# WX0_012_296DL_3.net
KiCad netlist of a schematic drawn in Altium Designer
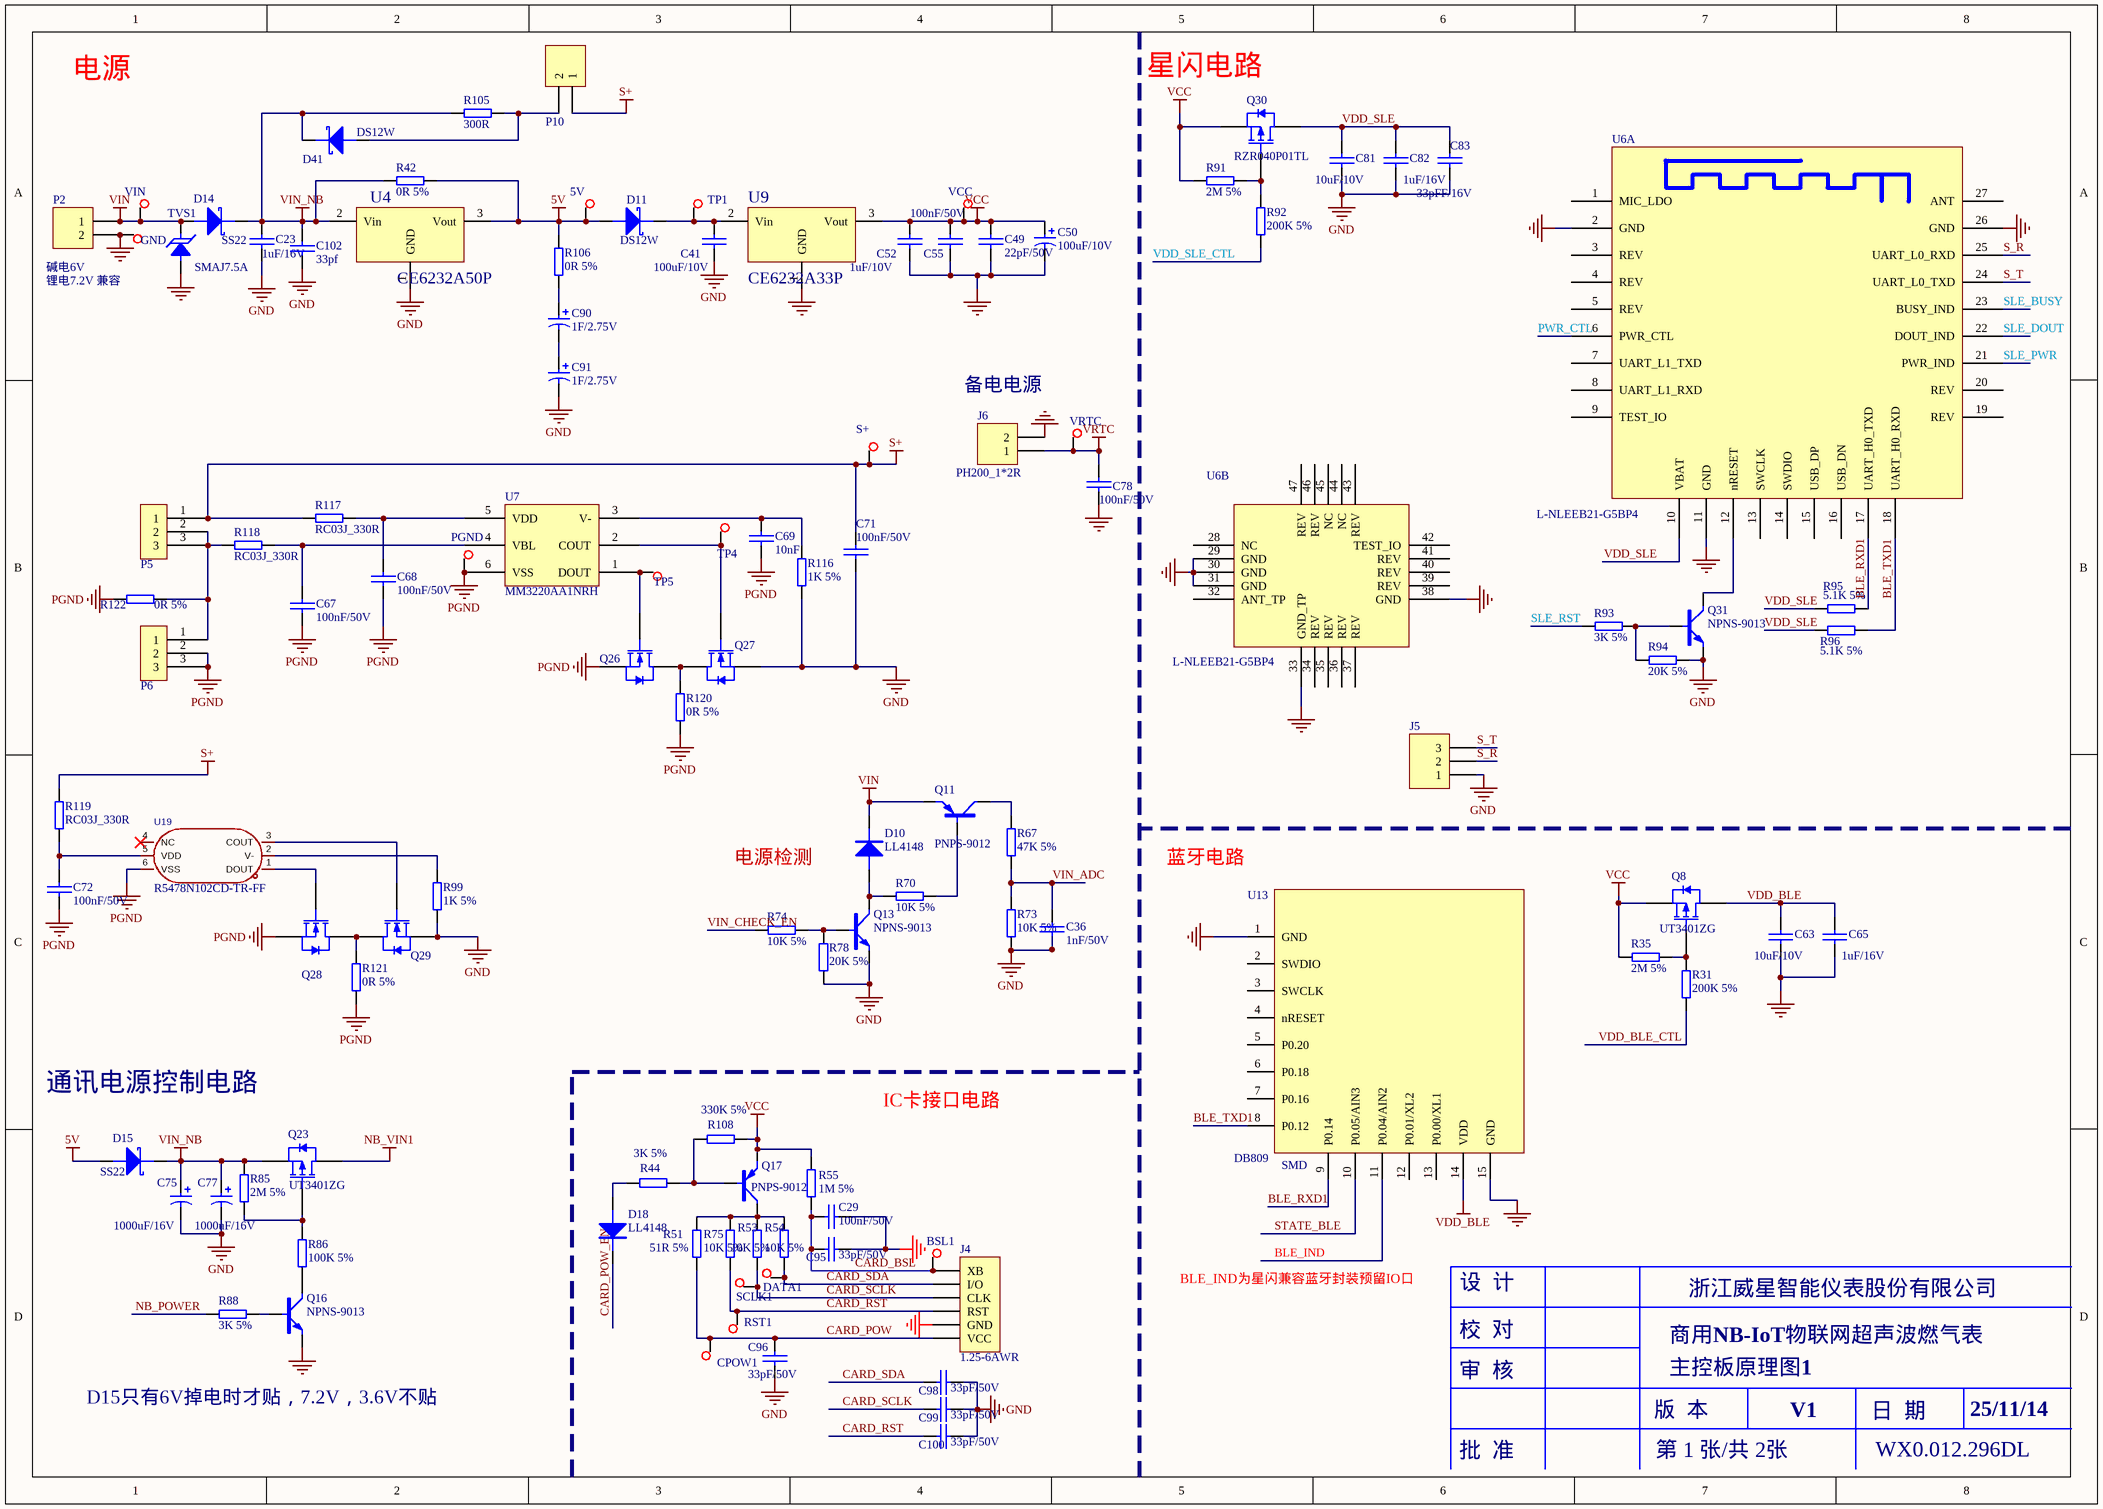
[diagram p0: WX0.012.296DL(3).SchDoc]

(export (version "E")
  (design (tool "Eeschema 10.0.6"))
  (components
    (comp (ref "5V")
      (value "TEST-PAD")
      (footprint "TEST-PAD")
      (description "单面焊盘测试点")
      (fields (field (name "PART NUMBER") "AD_WXHJ_TEST-PAD_01"))
      (libsource (lib "Database_Libs2") (part "TEST-PAD"))
    )
    (comp (ref "BSL1")
      (value "TEST-PAD")
      (footprint "TEST-PAD")
      (description "单面焊盘测试点")
      (fields (field (name "PART NUMBER") "AD_WXHJ_TEST-PAD_01"))
      (libsource (lib "Database_Libs2") (part "TEST-PAD"))
    )
    (comp (ref "C23")
      (value "1uF/16V")
      (footprint "CAP0603")
      (description "105pF,16 V,±10%,0603,国巨,CC0603KRX7R7BB105")
      (fields (field (name "PART NUMBER") "101020103-0003"))
      (libsource (lib "Database_Libs2") (part "CC03K7R7_1U"))
    )
    (comp (ref "C29")
      (value "100nF/50V")
      (footprint "CAP0603")
      (description "104pF,50 V,±10%,0603,国巨,CC0603KRX7R9BB104")
      (fields (field (name "PART NUMBER") "101020103-0021"))
      (libsource (lib "Database_Libs2") (part "CC03K7R9_100N"))
    )
    (comp (ref "C36")
      (value "1nF/50V")
      (footprint "CAP0603")
      (description "102pF,50 V,±10%,0603,国巨,CC0603KRX7R9BB102")
      (fields (field (name "PART NUMBER") "101020103-0022"))
      (libsource (lib "Database_Libs2") (part "CC03K7R9_1N"))
    )
    (comp (ref "C41")
      (value "100uF/10V")
      (footprint "GRM31CR60J107ME39L")
      (description "106pF,10 V,±10%,0603,村田,GRM188R61A106KE47D")
      (fields (field (name "PART NUMBER") "101020103-0026"))
      (libsource (lib "Database_Libs2") (part "CC03K5R6_10U"))
    )
    (comp (ref "C49")
      (value "22pF/50V")
      (footprint "CAP0603")
      (description "22pF,50 V,±5%,0603,国巨,CC0603JRNPO9BN22")
      (fields (field (name "PART NUMBER") "101020103-0009"))
      (libsource (lib "Database_Libs2") (part "CC03JPO9_22P"))
    )
    (comp (ref "C50")
      (value "100uF/10V")
      (footprint "GRM31CR60J107ME39L")
      (description "100UF,10 V,±20%,3528,AVX / KEMET,TAJB107M010RNJ")
      (fields (field (name "PART NUMBER") "1010205-0006"))
      (libsource (lib "Database_Libs2") (part "CT6MATAJ_100U"))
    )
    (comp (ref "C52")
      (value "1uF/10V")
      (footprint "CAP0603")
      (description "106pF,10 V,±10%,0603,村田,GRM188R61A106KE47D")
      (fields (field (name "PART NUMBER") "101020103-0026"))
      (libsource (lib "Database_Libs2") (part "CC03K5R6_10U"))
    )
    (comp (ref "C55")
      (value "100nF/50V")
      (footprint "CAP0603")
      (description "104pF,50 V,±10%,0603,国巨,CC0603KRX7R9BB104")
      (fields (field (name "PART NUMBER") "101020103-0021"))
      (libsource (lib "Database_Libs2") (part "CC03K7R9_100N"))
    )
    (comp (ref "C63")
      (value "10uF/10V")
      (footprint "CAP0603")
      (description "106pF,10 V,±10%,0603,村田,GRM188R61A106KE47D")
      (fields (field (name "PART NUMBER") "101020103-0026"))
      (libsource (lib "Database_Libs2") (part "CC03K5R6_10U"))
    )
    (comp (ref "C65")
      (value "1uF/16V")
      (footprint "CAP0603")
      (description "105pF,16 V,±10%,0603,国巨,CC0603KRX7R7BB105")
      (fields (field (name "PART NUMBER") "101020103-0003"))
      (libsource (lib "Database_Libs2") (part "CC03K7R7_1U"))
    )
    (comp (ref "C67")
      (value "100nF/50V")
      (footprint "CAP0603")
      (description "104pF,50 V,±10%,0603,国巨,CC0603KRX7R9BB104")
      (fields (field (name "PART NUMBER") "101020103-0021"))
      (libsource (lib "Database_Libs1") (part "CC03K7R9_100N"))
    )
    (comp (ref "C68")
      (value "100nF/50V")
      (footprint "CAP0603")
      (description "104pF,50 V,±10%,0603,国巨,CC0603KRX7R9BB104")
      (fields (field (name "PART NUMBER") "101020103-0021"))
      (libsource (lib "Database_Libs1") (part "CC03K7R9_100N"))
    )
    (comp (ref "C69")
      (value "10nF")
      (footprint "CAP0603")
      (description "103pF,50 V,±10%,0603,国巨,CC0603KRX7R9BB104")
      (libsource (lib "Database_Libs1") (part "CC03K7R9_100N"))
    )
    (comp (ref "C71")
      (value "100nF/50V")
      (footprint "CAP0603")
      (description "104pF,50 V,±10%,0603,国巨,CC0603KRX7R9BB104")
      (fields (field (name "PART NUMBER") "101020103-0021"))
      (libsource (lib "Database_Libs1") (part "CC03K7R9_100N"))
    )
    (comp (ref "C72")
      (value "100nF/50V")
      (footprint "CAP0603")
      (description "104pF,50 V,±10%,0603,国巨,CC0603KRX7R9BB104")
      (fields (field (name "PART NUMBER") "101020103-0021"))
      (libsource (lib "Database_Libs1") (part "CC03K7R9_100N"))
    )
    (comp (ref "C75")
      (value "1000uF/16V")
      (footprint "CAP-SMD_BD10.0-L10.3-W10.3-FD")
      (description "1000uF,16 V,±20%,8*20mm,Rubycon,16ZLH1000M")
      (fields (field (name "PART NUMBER") "1010203-0029"))
      (libsource (lib "Database_Libs2") (part "CAL7MRZLH_1000U_R"))
    )
    (comp (ref "C77")
      (value "1000uF/16V")
      (footprint "CAP-SMD_BD10.0-L10.3-W10.3-FD")
      (description "1000uF,16 V,±20%,8*20mm,Rubycon,16ZLH1000M")
      (fields (field (name "PART NUMBER") "1010203-0029"))
      (libsource (lib "Database_Libs2") (part "CAL7MRZLH_1000U_R"))
    )
    (comp (ref "C78")
      (value "100nF/50V")
      (footprint "CAP0603")
      (description "104pF,50 V,±10%,0603,国巨,CC0603KRX7R9BB104")
      (fields (field (name "PART NUMBER") "101020103-0021"))
      (libsource (lib "Database_Libs2") (part "CC03K7R9_100N"))
    )
    (comp (ref "C81")
      (value "10uF/10V")
      (footprint "CAP0603")
      (description "106pF,10 V,±10%,0603,村田,GRM188R61A106KE47D")
      (fields (field (name "PART NUMBER") "101020103-0026"))
      (libsource (lib "Database_Libs2") (part "CC03K5R6_10U"))
    )
    (comp (ref "C82")
      (value "1uF/16V")
      (footprint "CAP0603")
      (description "105pF,16 V,±10%,0603,国巨,CC0603KRX7R7BB105")
      (fields (field (name "PART NUMBER") "101020103-0003"))
      (libsource (lib "Database_Libs2") (part "CC03K7R7_1U"))
    )
    (comp (ref "C83")
      (value "33pFF/16V")
      (footprint "CAP0603")
      (description "105pF,16 V,±10%,0603,国巨,CC0603KRX7R7BB105")
      (fields (field (name "PART NUMBER") "101020103-0003"))
      (libsource (lib "Database_Libs2") (part "CC03K7R7_1U"))
    )
    (comp (ref "C90")
      (value "1F/2.75V")
      (footprint "CAPPC_350_800_1600")
      (description "1F,2.75 V,-20%~+20%,8mm*16mm,红宝石,2.7 DMC 1 M MY4 8X16")
      (fields (field (name "PART NUMBER") "1010202-0015"))
      (libsource (lib "Database_Libs2") (part "CALM3MRDMC_1F"))
    )
    (comp (ref "C91")
      (value "1F/2.75V")
      (footprint "CAPPC_350_800_1600")
      (description "1F,2.75 V,-20%~+20%,8mm*16mm,红宝石,2.7 DMC 1 M MY4 8X16")
      (fields (field (name "PART NUMBER") "1010202-0015"))
      (libsource (lib "Database_Libs2") (part "CALM3MRDMC_1F"))
    )
    (comp (ref "C95")
      (value "33pF/50V")
      (footprint "CAP0603")
      (description "33pF,50 V,±10%,0603,国巨,CC0603KRNPO9BN33")
      (fields (field (name "PART NUMBER") "101020103-0027"))
      (libsource (lib "Database_Libs2") (part "CC03KPO9_33P"))
    )
    (comp (ref "C96")
      (value "33pF/50V")
      (footprint "CAP0603")
      (description "33pF,50 V,±10%,0603,国巨,CC0603KRNPO9BN33")
      (fields (field (name "PART NUMBER") "101020103-0027"))
      (libsource (lib "Database_Libs2") (part "CC03KPO9_33P"))
    )
    (comp (ref "C98")
      (value "33pF/50V")
      (footprint "CAP0603")
      (description "33pF,50 V,±10%,0603,国巨,CC0603KRNPO9BN33")
      (fields (field (name "PART NUMBER") "101020103-0027"))
      (libsource (lib "Database_Libs2") (part "CC03KPO9_33P"))
    )
    (comp (ref "C99")
      (value "33pF/50V")
      (footprint "CAP0603")
      (description "33pF,50 V,±10%,0603,国巨,CC0603KRNPO9BN33")
      (fields (field (name "PART NUMBER") "101020103-0027"))
      (libsource (lib "Database_Libs2") (part "CC03KPO9_33P"))
    )
    (comp (ref "C100")
      (value "33pF/50V")
      (footprint "CAP0603")
      (description "33pF,50 V,±10%,0603,国巨,CC0603KRNPO9BN33")
      (fields (field (name "PART NUMBER") "101020103-0027"))
      (libsource (lib "Database_Libs2") (part "CC03KPO9_33P"))
    )
    (comp (ref "C102")
      (value "33pf")
      (footprint "CAP0603")
      (description "105pF,16 V,±10%,0603,国巨,CC0603KRX7R7BB105")
      (fields (field (name "PART NUMBER") "101020103-0003"))
      (libsource (lib "Database_Libs2") (part "CC03K7R7_1U"))
    )
    (comp (ref "CPOW1")
      (value "TEST-PAD")
      (footprint "TEST-PAD")
      (description "单面焊盘测试点")
      (fields (field (name "PART NUMBER") "AD_WXHJ_TEST-PAD_01"))
      (libsource (lib "Database_Libs2") (part "TEST-PAD"))
    )
    (comp (ref "D10")
      (value "LL4148")
      (footprint "SOD-123FL")
      (description "4148,4148,0.2 A,1 V,100 V,先科,LL4148")
      (fields (field (name "PART NUMBER") "101040101-0005"))
      (libsource (lib "Database_Libs2") (part "02_LL4148"))
    )
    (comp (ref "D11")
      (value "DS12W")
      (footprint "SOD-123FL")
      (description "DS12W,SOD-123FL,1 A,0.55 V,20 V,领晨科技,DS12W")
      (fields (field (name "PART NUMBER") "101040101-0048"))
      (libsource (lib "Database_Libs2") (part "02_DS12W"))
    )
    (comp (ref "D14")
      (value "SS22")
      (footprint "DO-214AC")
      (description "SS12,DO-214AC,1 A,0.55 V,20 V,昶鑫,SS12")
      (fields (field (name "PART NUMBER") "101040101-0009"))
      (libsource (lib "Database_Libs2") (part "02_SS12"))
    )
    (comp (ref "D15")
      (value "SS22")
      (footprint "DO-214AC")
      (description "SS12,DO-214AC,1 A,0.55 V,20 V,昶鑫,SS12")
      (fields (field (name "PART NUMBER") "101040101-0009"))
      (libsource (lib "Database_Libs2") (part "02_SS12"))
    )
    (comp (ref "D18")
      (value "LL4148")
      (footprint "SOD-123FL")
      (description "4148,4148,0.2 A,1 V,100 V,先科,LL4148")
      (fields (field (name "PART NUMBER") "101040101-0005"))
      (libsource (lib "Database_Libs2") (part "02_LL4148"))
    )
    (comp (ref "D41")
      (value "DS12W")
      (footprint "SOD-123FL")
      (description "DS12W,SOD-123FL,1 A,0.55 V,20 V,领晨科技,DS12W")
      (fields (field (name "PART NUMBER") "101040101-0048"))
      (libsource (lib "Database_Libs2") (part "02_DS12W"))
    )
    (comp (ref "DATA1")
      (value "TEST-PAD")
      (footprint "TEST-PAD")
      (description "单面焊盘测试点")
      (fields (field (name "PART NUMBER") "AD_WXHJ_TEST-PAD_01"))
      (libsource (lib "Database_Libs2") (part "TEST-PAD"))
    )
    (comp (ref "GND")
      (value "TEST-PAD")
      (footprint "TEST-PAD")
      (description "单面焊盘测试点")
      (fields (field (name "PART NUMBER") "AD_WXHJ_TEST-PAD_01"))
      (libsource (lib "Database_Libs2") (part "TEST-PAD"))
    )
    (comp (ref "J4")
      (value "1.25-6AWR")
      (footprint "SMT-1.25-6")
      (description "1.25-6AWR 卷,6针1.25mm,母头,单排,贴片卧式")
      (fields (field (name "PART NUMBER") "1010902-0121"))
      (libsource (lib "Database_Libs2") (part "CARD1608"))
    )
    (comp (ref "J5")
      (value "PIN254_1*3")
      (footprint "PIN254_1*3*WXHJ")
      (libsource (lib "Connect_WX") (part "PIN254_1*3"))
    )
    (comp (ref "J6")
      (value "PH200_1*2R")
      (footprint "WX0.008.919PCB-4.2:BAT")
      (description "2.0-2AW,直插弯座，2PIN，脚间距2mm，带防翘起,公头,单排,2.0-2AW;直插弯座，2PIN,脚间距2mm，带防翘起")
      (fields (field (name "PART NUMBER") "1010902-0105"))
      (libsource (lib "Database_Libs2") (part "PH200_1*2R"))
    )
    (comp (ref "P2")
      (value "碱电6V")
      (footprint "Header 2")
      (description "2.0-2AW,直插弯座，2PIN，脚间距2mm，带防翘起,公头,单排,2.0-2AW;直插弯座，2PIN,脚间距2mm，带防翘起")
      (fields (field (name "PART NUMBER") "1010902-0105"))
      (libsource (lib "Database_Libs1") (part "PH200_1*2R"))
    )
    (comp (ref "P5")
      (value "ER14250")
      (footprint "WX0.009.158PCB-4.2:SPC1520_3")
      (description "F0005Q-LF,1200 mA*h,0,3.6 V,带连接片,1/2AA,不能充电,85 ℃,-60 ℃,ER14250,惠州亿纬锂能股份有限公司")
      (fields (field (name "PART NUMBER") "1011101-0203"))
      (libsource (lib "Database_Libs1") (part "04_BAT1_ER14250_3.6V_3"))
    )
    (comp (ref "P6")
      (value "ER14250")
      (footprint "WX0.009.158PCB-4.2:SPC1520_3")
      (description "F0005Q-LF,1200 mA*h,0,3.6 V,带连接片,1/2AA,不能充电,85 ℃,-60 ℃,ER14250,惠州亿纬锂能股份有限公司")
      (fields (field (name "PART NUMBER") "1011101-0203"))
      (libsource (lib "Database_Libs1") (part "04_BAT1_ER14250_3.6V_3"))
    )
    (comp (ref "P10")
      (value "PH2.0-2P")
      (footprint "WX0.007.406PCB-4.2:PCBComponent_1 - duplicate2")
      (description "PH2.0-2P,2mm间距,母头,单排,PH2.0-2P")
      (fields (field (name "PART NUMBER") "1010902-0117"))
      (libsource (lib "Database_Libs2") (part "PH2.0-2P"))
    )
    (comp (ref "PGND")
      (value "TEST-PAD")
      (footprint "TEST-PAD")
      (description "单面焊盘测试点")
      (fields (field (name "PART NUMBER") "AD_WXHJ_TEST-PAD_01"))
      (libsource (lib "Database_Libs2") (part "TEST-PAD"))
    )
    (comp (ref "Q8")
      (value "UT3401ZG")
      (footprint "SOT-23")
      (description "UT3401ZG,P-MOS,SOT-23,UTC,UT3401ZG")
      (fields (field (name "PART NUMBER") "101040201-0013"))
      (libsource (lib "Database_Libs2") (part "03_P-UT3401ZG"))
    )
    (comp (ref "Q11")
      (value "PNPS-9012")
      (footprint "SOT-23")
      (description "9012,PNP,SOT-23,JCET;长电,S9012")
      (fields (field (name "PART NUMBER") "101040201-0001"))
      (libsource (lib "Database_Libs2") (part "03_PNPS-9012"))
    )
    (comp (ref "Q13")
      (value "NPNS-9013")
      (footprint "SOT-23")
      (description "9013,NPN,SOT-23,长电,S9013")
      (fields (field (name "PART NUMBER") "101040201-0002"))
      (libsource (lib "Database_Libs2") (part "03_NPNS-9013"))
    )
    (comp (ref "Q16")
      (value "NPNS-9013")
      (footprint "SOT-23")
      (description "9013,NPN,SOT-23,长电,S9013")
      (fields (field (name "PART NUMBER") "101040201-0002"))
      (libsource (lib "Database_Libs2") (part "03_NPNS-9013"))
    )
    (comp (ref "Q17")
      (value "PNPS-9012")
      (footprint "SOT-23")
      (description "9012,PNP,SOT-23,JCET;长电,S9012")
      (fields (field (name "PART NUMBER") "101040201-0001"))
      (libsource (lib "Database_Libs2") (part "03_PNPS-9012"))
    )
    (comp (ref "Q23")
      (value "UT3401ZG")
      (footprint "SOT-23")
      (description "UT3401ZG,P-MOS,SOT-23,UTC,UT3401ZG")
      (fields (field (name "PART NUMBER") "101040201-0013"))
      (libsource (lib "Database_Libs2") (part "03_P-UT3401ZG"))
    )
    (comp (ref "Q26")
      (value "RTR025N03TL")
      (footprint "SOT-23")
      (fields (field (name "PART NUMBER") "101040201-0012"))
      (libsource (lib "Database_Libs1") (part "03_N-RTR025N03TL"))
    )
    (comp (ref "Q27")
      (value "RTR025N03TL")
      (footprint "SOT-23")
      (fields (field (name "PART NUMBER") "101040201-0012"))
      (libsource (lib "Database_Libs1") (part "03_N-RTR025N03TL"))
    )
    (comp (ref "Q28")
      (value "RTR025N03TL")
      (footprint "SOT-23")
      (fields (field (name "PART NUMBER") "101040201-0012"))
      (libsource (lib "Database_Libs1") (part "03_N-RTR025N03TL"))
    )
    (comp (ref "Q29")
      (value "RTR025N03TL")
      (footprint "SOT-23")
      (fields (field (name "PART NUMBER") "101040201-0012"))
      (libsource (lib "Database_Libs1") (part "03_N-RTR025N03TL"))
    )
    (comp (ref "Q30")
      (value "RZR040P01TL")
      (footprint "SOT-23")
      (description "RZR040P01TL；1.5v导通,P-MOS,SOT-23,罗姆,RZR040P01TL")
      (fields (field (name "PART NUMBER") "101040201-0010"))
      (libsource (lib "Database_Libs2") (part "03_P-RZR040P01TL"))
    )
    (comp (ref "Q31")
      (value "NPNS-9013")
      (footprint "SOT-23")
      (description "9013,NPN,SOT-23,长电,S9013")
      (fields (field (name "PART NUMBER") "101040201-0002"))
      (libsource (lib "Database_Libs2") (part "03_NPNS-9013"))
    )
    (comp (ref "R31")
      (value "200K 5%")
      (footprint "RES0603")
      (description "10K±5%,1/10W,0603")
      (fields (field (name "PART NUMBER") "101010103-0003"))
      (libsource (lib "Database_Libs1") (part "RC03JF_10K"))
    )
    (comp (ref "R35")
      (value "2M 5%")
      (footprint "RES0603")
      (description "10K±5%,1/10W,0603")
      (fields (field (name "PART NUMBER") "101010103-0003"))
      (libsource (lib "Database_Libs1") (part "RC03JF_10K"))
    )
    (comp (ref "R42")
      (value "0R 5%")
      (footprint "RES1206")
      (description "0Ω,±5%,1/4W,1206,国巨,RC1206JR-070RL")
      (fields (field (name "PART NUMBER") "101010101-0013"))
      (libsource (lib "Database_Libs2") (part "RC06J_0R"))
    )
    (comp (ref "R44")
      (value "3K 5%")
      (footprint "RES0603")
      (description "国巨,±5%,0603,,155 ℃,-55 ℃,RC0603JR-073KL,无铅,100 ppm/℃,1/10W,,3K")
      (fields (field (name "PART NUMBER") "101010103-0006"))
      (libsource (lib "Database_Libs2") (part "RC03J_3K"))
    )
    (comp (ref "R51")
      (value "51R 5%")
      (footprint "RES1206")
      (description "51Ω,±5%,1/4W,1206,国巨,RC1206JR-0751RL")
      (fields (field (name "PART NUMBER") "101010101-0029"))
      (libsource (lib "Database_Libs2") (part "RC06F_51R"))
    )
    (comp (ref "R53")
      (value "10K 5%")
      (footprint "RES0603")
      (description "国巨,±5%,0603,,155 ℃,-55 ℃,RC0603JR-0710KL,无铅,200 ppm/℃,1/10W,,10K")
      (fields (field (name "PART NUMBER") "101010103-0003"))
      (libsource (lib "Database_Libs2") (part "RC03J_10K"))
    )
    (comp (ref "R54")
      (value "10K 5%")
      (footprint "RES0603")
      (description "国巨,±5%,0603,,155 ℃,-55 ℃,RC0603JR-0710KL,无铅,200 ppm/℃,1/10W,,10K")
      (fields (field (name "PART NUMBER") "101010103-0003"))
      (libsource (lib "Database_Libs2") (part "RC03J_10K"))
    )
    (comp (ref "R55")
      (value "1M 5%")
      (footprint "RES0603")
      (description "国巨,±5%,0603,,155 ℃,-55 ℃,RC0603JR-071ML,无铅,200 ppm/℃,1/10W,,1M")
      (fields (field (name "PART NUMBER") "101010103-0002"))
      (libsource (lib "Database_Libs2") (part "RC03J_1M"))
    )
    (comp (ref "R67")
      (value "47K 5%")
      (footprint "RES0603")
      (description "47K,±5%,1/10W,0603,国巨,RC0603JR-0747KL")
      (fields (field (name "PART NUMBER") "101010103-0012"))
      (libsource (lib "Database_Libs2") (part "RC03J_47K"))
    )
    (comp (ref "R70")
      (value "10K 5%")
      (footprint "RES0603")
      (description "国巨,±5%,0603,,155 ℃,-55 ℃,RC0603JR-0710KL,无铅,200 ppm/℃,1/10W,,10K")
      (fields (field (name "PART NUMBER") "101010103-0003"))
      (libsource (lib "Database_Libs2") (part "RC03J_10K"))
    )
    (comp (ref "R73")
      (value "10K 5%")
      (footprint "RES0603")
      (description "国巨,±5%,0603,,155 ℃,-55 ℃,RC0603JR-0710KL,无铅,200 ppm/℃,1/10W,,10K")
      (fields (field (name "PART NUMBER") "101010103-0003"))
      (libsource (lib "Database_Libs2") (part "RC03J_10K"))
    )
    (comp (ref "R74")
      (value "10K 5%")
      (footprint "RES0603")
      (description "国巨,±5%,0603,,155 ℃,-55 ℃,RC0603JR-0710KL,无铅,200 ppm/℃,1/10W,,10K")
      (fields (field (name "PART NUMBER") "101010103-0003"))
      (libsource (lib "Database_Libs2") (part "RC03J_10K"))
    )
    (comp (ref "R75")
      (value "10K 5%")
      (footprint "RES0603")
      (description "国巨,±5%,0603,,155 ℃,-55 ℃,RC0603JR-0710KL,无铅,200 ppm/℃,1/10W,,10K")
      (fields (field (name "PART NUMBER") "101010103-0003"))
      (libsource (lib "Database_Libs2") (part "RC03J_10K"))
    )
    (comp (ref "R78")
      (value "20K 5%")
      (footprint "RES0603")
      (description "国巨,±5%,0603,,155 ℃,-55 ℃,RC0603JR-0720KL,无铅,200 ppm/℃,1/10W,,20K")
      (fields (field (name "PART NUMBER") "101010103-0004"))
      (libsource (lib "Database_Libs2") (part "RC03J_20K"))
    )
    (comp (ref "R85")
      (value "2M 5%")
      (footprint "RES0603")
      (description "国巨,±5%,0603,,155 ℃,-55 ℃,RC0603JR-072ML,含铅,100 ppm/℃,1/10W,,2M")
      (fields (field (name "PART NUMBER") "101010103-0025"))
      (libsource (lib "Database_Libs2") (part "RC03J_2M"))
    )
    (comp (ref "R86")
      (value "100K 5%")
      (footprint "RES0603")
      (description "国巨,±5%,0603,,155 ℃,-55 ℃,RC0603JR-07100KL,无铅,100 ppm/℃,1/10W,,100K")
      (fields (field (name "PART NUMBER") "101010103-0005"))
      (libsource (lib "Database_Libs2") (part "RC03J_100K"))
    )
    (comp (ref "R88")
      (value "3K 5%")
      (footprint "RES0603")
      (description "国巨,±5%,0603,,155 ℃,-55 ℃,RC0603JR-073KL,无铅,100 ppm/℃,1/10W,,3K")
      (fields (field (name "PART NUMBER") "101010103-0006"))
      (libsource (lib "Database_Libs2") (part "RC03J_3K"))
    )
    (comp (ref "R91")
      (value "2M 5%")
      (footprint "RES0603")
      (description "国巨,±5%,0603,,155 ℃,-55 ℃,RC0603JR-072ML,含铅,100 ppm/℃,1/10W,,2M")
      (fields (field (name "PART NUMBER") "101010103-0025"))
      (libsource (lib "Database_Libs2") (part "RC03J_2M"))
    )
    (comp (ref "R92")
      (value "200K 5%")
      (footprint "RES0603")
      (description "200K,±5%,1/10W,0603,国巨,RC0603JR-07200KL")
      (fields (field (name "PART NUMBER") "101010103-0034"))
      (libsource (lib "Database_Libs2") (part "RC03J_200K"))
    )
    (comp (ref "R93")
      (value "3K 5%")
      (footprint "RES0603")
      (description "国巨,±5%,0603,,155 ℃,-55 ℃,RC0603JR-073KL,无铅,100 ppm/℃,1/10W,,3K")
      (fields (field (name "PART NUMBER") "101010103-0006"))
      (libsource (lib "Database_Libs2") (part "RC03J_3K"))
    )
    (comp (ref "R94")
      (value "20K 5%")
      (footprint "RES0603")
      (description "国巨,±5%,0603,,155 ℃,-55 ℃,RC0603JR-0720KL,无铅,200 ppm/℃,1/10W,,20K")
      (fields (field (name "PART NUMBER") "101010103-0004"))
      (libsource (lib "Database_Libs2") (part "RC03J_20K"))
    )
    (comp (ref "R95")
      (value "5.1K 5%")
      (footprint "RES0603")
      (description "国巨,±5%,0603,,155 ℃,55 ℃,RC0603JR-075.1KL,无铅,200 ppm/℃,1/10W,,5.1k")
      (fields (field (name "PART NUMBER") "101010103-0015"))
      (libsource (lib "Database_Libs2") (part "RC03J_5.1K"))
    )
    (comp (ref "R96")
      (value "5.1K 5%")
      (footprint "RES0603")
      (description "国巨,±5%,0603,,155 ℃,55 ℃,RC0603JR-075.1KL,无铅,200 ppm/℃,1/10W,,5.1k")
      (fields (field (name "PART NUMBER") "101010103-0015"))
      (libsource (lib "Database_Libs2") (part "RC03J_5.1K"))
    )
    (comp (ref "R99")
      (value "1K 5%")
      (footprint "RES0603")
      (description "1K,±5%,1/10W,0603,国巨,RC0603JR-071KL")
      (fields (field (name "PART NUMBER") "101010103-0008"))
      (libsource (lib "Database_Libs1") (part "RC03J_1K"))
    )
    (comp (ref "R105")
      (value "300R")
      (footprint "RES1206")
      (description "100R,±5%,1/10W,0603,国巨,RC0603JR-07100RL")
      (fields (field (name "PART NUMBER") "101010103-0022"))
      (libsource (lib "Database_Libs2") (part "RC03J_100R"))
    )
    (comp (ref "R106")
      (value "0R 5%")
      (footprint "RES0603")
      (description "国巨,±5%,0603,,155 ℃,-55 ℃,RC0603J2-070RL,无铅,200 ppm/℃,1/10W,,0R")
      (fields (field (name "PART NUMBER") "101010103-0001"))
      (libsource (lib "Database_Libs2") (part "RC03J_0R"))
    )
    (comp (ref "R108")
      (value "330K 5%")
      (footprint "RES0603")
      (description "国巨,±5%,0603,,155 ℃,-55 ℃,RC0603JR-073KL,无铅,100 ppm/℃,1/10W,,3K")
      (fields (field (name "PART NUMBER") "101010103-0006"))
      (libsource (lib "Database_Libs2") (part "RC03J_3K"))
    )
    (comp (ref "R116")
      (value "1K 5%")
      (footprint "RES0603")
      (description "1K,±5%,1/10W,0603,国巨,RC0603JR-071KL")
      (fields (field (name "PART NUMBER") "101010103-0008"))
      (libsource (lib "Database_Libs1") (part "RC03J_1K"))
    )
    (comp (ref "R117")
      (value "RC03J_330R")
      (footprint "RES1206")
      (libsource (lib "Resistor_WX") (part "RC03J_330R"))
    )
    (comp (ref "R118")
      (value "RC03J_330R")
      (footprint "RES1206")
      (libsource (lib "Resistor_WX") (part "RC03J_330R"))
    )
    (comp (ref "R119")
      (value "RC03J_330R")
      (footprint "RES1206")
      (libsource (lib "Resistor_WX") (part "RC03J_330R"))
    )
    (comp (ref "R120")
      (value "0R 5%")
      (footprint "RES0603")
      (description "国巨,±5%,0603,,155 ℃,-55 ℃,RC0603J2-070RL,无铅,200 ppm/℃,1/10W,,0R")
      (fields (field (name "PART NUMBER") "101010103-0001"))
      (libsource (lib "Database_Libs2") (part "RC03J_0R"))
    )
    (comp (ref "R121")
      (value "0R 5%")
      (footprint "RES0603")
      (description "国巨,±5%,0603,,155 ℃,-55 ℃,RC0603J2-070RL,无铅,200 ppm/℃,1/10W,,0R")
      (fields (field (name "PART NUMBER") "101010103-0001"))
      (libsource (lib "Database_Libs2") (part "RC03J_0R"))
    )
    (comp (ref "R122")
      (value "0R 5%")
      (footprint "RES0603")
      (description "国巨,±5%,0603,,155 ℃,-55 ℃,RC0603J2-070RL,无铅,200 ppm/℃,1/10W,,0R")
      (fields (field (name "PART NUMBER") "101010103-0001"))
      (libsource (lib "Database_Libs2") (part "RC03J_0R"))
    )
    (comp (ref "RST1")
      (value "TEST-PAD")
      (footprint "TEST-PAD")
      (description "单面焊盘测试点")
      (fields (field (name "PART NUMBER") "AD_WXHJ_TEST-PAD_01"))
      (libsource (lib "Database_Libs2") (part "TEST-PAD"))
    )
    (comp (ref "S+")
      (value "TEST-PAD")
      (footprint "TEST-PAD")
      (description "单面焊盘测试点")
      (fields (field (name "PART NUMBER") "AD_WXHJ_TEST-PAD_01"))
      (libsource (lib "Database_Libs2") (part "TEST-PAD"))
    )
    (comp (ref "SCLK1")
      (value "TEST-PAD")
      (footprint "TEST-PAD")
      (description "单面焊盘测试点")
      (fields (field (name "PART NUMBER") "AD_WXHJ_TEST-PAD_01"))
      (libsource (lib "Database_Libs2") (part "TEST-PAD"))
    )
    (comp (ref "TP1")
      (value "TEST-PAD")
      (footprint "TEST-PAD")
      (description "单面焊盘测试点")
      (fields (field (name "PART NUMBER") "AD_WXHJ_TEST-PAD_01"))
      (libsource (lib "Database_Libs2") (part "TEST-PAD"))
    )
    (comp (ref "TP4")
      (value "TEST-PAD")
      (footprint "TEST-PAD")
      (description "单面焊盘测试点")
      (fields (field (name "PART NUMBER") "AD_WXHJ_TEST-PAD_01"))
      (libsource (lib "Database_Libs2") (part "TEST-PAD"))
    )
    (comp (ref "TP5")
      (value "TEST-PAD")
      (footprint "TEST-PAD")
      (description "单面焊盘测试点")
      (fields (field (name "PART NUMBER") "AD_WXHJ_TEST-PAD_01"))
      (libsource (lib "Database_Libs2") (part "TEST-PAD"))
    )
    (comp (ref "TVS1")
      (value "SMAJ7.5A")
      (footprint "PCBComponent_1 - duplicate4")
      (description "SMBJ6.0CA,DO-214AA,10.3 V,6.0 V,600 W,58.3 A,800 uA,上海君耀电子有限公司,SMBJ6.0CA")
      (fields (field (name "PART NUMBER") "101040101-0024"))
      (libsource (lib "Database_Libs2") (part "05_SMBJ6.0CA"))
    )
    (comp (ref "U4")
      (value "CE6232A50P")
      (footprint "SOT-89")
      (description "CE6232A50P,CE6232A50P,SOT89-3,8 V,1.8 V,0.11 V,5 V,500mA,0.8 uA,南京芯力微电子有限公司")
      (fields (field (name "PART NUMBER") "1010503-0028"))
      (libsource (lib "Database_Libs2") (part "02_CE6232A50P"))
    )
    (comp (ref "U6")
      (value "L-NLEEB21-G5BP4")
      (footprint "24V星闪电磁阀控制器主控线路板1:L-NLEEB21-G5BP4")
      (libsource (lib "L-NLEEB21-G5BP4_V03") (part "L-NLEEB21-G5BP4"))
    )
    (comp (ref "U7")
      (value "MM3220AA1NRH")
      (footprint "SOT-23-6")
      (libsource (lib "Chip_WX") (part "MM3220AA1NRH"))
    )
    (comp (ref "U9")
      (value "CE6232A33P")
      (footprint "SOT-89")
      (description "CE6232-3.3,CE6232-3.3,SOT89-3,8V,1.8V,0.11V,3.3V,300mA,0.8uA,南京芯力微电子有限公司")
      (fields (field (name "PART NUMBER") "1010503-0029"))
      (libsource (lib "Database_Libs2") (part "02_CE6232A33P"))
    )
    (comp (ref "U13")
      (value "DB809")
      (footprint "DB809")
      (description "北高智蓝牙模块DB809")
      (fields (field (name "PART NUMBER") "1011402-0194") (field (name "SMD/DIP") "SMD"))
      (libsource (lib "Database_Libs2") (part "01_DB809"))
    )
    (comp (ref "U19")
      (value "R5478N102CD-TR-FF")
      (footprint "SOT-23-6_L2.9-W1.6-P0.95-LS2.8-BL (1):SOT-23-6_L2.9-W1.6-P0.95-LS2.8-BL")
      (libsource (lib "altium-import") (part "root_2_R5478N102CD-TR-FF_"))
    )
    (comp (ref "VCC")
      (value "TEST-PAD")
      (footprint "TEST-PAD")
      (description "单面焊盘测试点")
      (fields (field (name "PART NUMBER") "AD_WXHJ_TEST-PAD_01"))
      (libsource (lib "Database_Libs2") (part "TEST-PAD"))
    )
    (comp (ref "VIN")
      (value "TEST-PAD")
      (footprint "TEST-PAD")
      (description "单面焊盘测试点")
      (fields (field (name "PART NUMBER") "AD_WXHJ_TEST-PAD_01"))
      (libsource (lib "Database_Libs2") (part "TEST-PAD"))
    )
    (comp (ref "VRTC")
      (value "TEST-PAD")
      (footprint "TEST-PAD")
      (description "单面焊盘测试点")
      (fields (field (name "PART NUMBER") "AD_WXHJ_TEST-PAD_01"))
      (libsource (lib "Database_Libs2") (part "TEST-PAD"))
    )
  )
  (nets
    (net (code "1") (name "/BLE_IND") (class "Default")
      (node (ref "U13") (pin "11") (pinfunction "P0.04/AIN2_11") (pintype "passive"))
    )
    (net (code "2") (name "/BLE_RXD1") (class "Default")
      (node (ref "R95") (pin "2") (pinfunction "2_2") (pintype "passive"))
      (node (ref "U13") (pin "9") (pinfunction "P0.14_9") (pintype "passive"))
      (node (ref "U6") (pin "17") (pinfunction "UART_H0_TXD_17") (pintype "passive"))
    )
    (net (code "3") (name "/BLE_TXD1") (class "Default")
      (node (ref "R96") (pin "2") (pinfunction "2_2") (pintype "passive"))
      (node (ref "U13") (pin "8") (pinfunction "P0.12_8") (pintype "passive"))
      (node (ref "U6") (pin "18") (pinfunction "UART_H0_RXD_18") (pintype "passive"))
    )
    (net (code "4") (name "/CARD_BSL") (class "Default")
      (node (ref "BSL1") (pin "1") (pinfunction "1_1") (pintype "passive"))
      (node (ref "C29") (pin "2") (pinfunction "2_2") (pintype "passive"))
      (node (ref "C95") (pin "1") (pinfunction "1_1") (pintype "passive"))
      (node (ref "J4") (pin "1") (pinfunction "XB_1") (pintype "passive"))
      (node (ref "R55") (pin "1") (pinfunction "1_1") (pintype "passive"))
    )
    (net (code "5") (name "/CARD_POW") (class "Default")
      (node (ref "C96") (pin "2") (pinfunction "2_2") (pintype "passive"))
      (node (ref "CPOW1") (pin "1") (pinfunction "1_1") (pintype "passive"))
      (node (ref "J4") (pin "6") (pinfunction "VCC_6") (pintype "passive"))
      (node (ref "R51") (pin "1") (pinfunction "1_1") (pintype "passive"))
    )
    (net (code "6") (name "/CARD_POW_EN") (class "Default")
      (node (ref "D18") (pin "2") (pinfunction "2_2") (pintype "passive"))
    )
    (net (code "7") (name "/CARD_RST") (class "Default")
      (node (ref "C100") (pin "1") (pinfunction "1_1") (pintype "passive"))
      (node (ref "J4") (pin "4") (pinfunction "RST_4") (pintype "passive"))
      (node (ref "R75") (pin "2") (pinfunction "2_2") (pintype "passive"))
      (node (ref "RST1") (pin "1") (pinfunction "1_1") (pintype "passive"))
    )
    (net (code "8") (name "/CARD_SCLK") (class "Default")
      (node (ref "C99") (pin "1") (pinfunction "1_1") (pintype "passive"))
      (node (ref "J4") (pin "3") (pinfunction "CLK_3") (pintype "passive"))
      (node (ref "R53") (pin "2") (pinfunction "2_2") (pintype "passive"))
      (node (ref "SCLK1") (pin "1") (pinfunction "1_1") (pintype "passive"))
    )
    (net (code "9") (name "/CARD_SDA") (class "Default")
      (node (ref "C98") (pin "1") (pinfunction "1_1") (pintype "passive"))
      (node (ref "DATA1") (pin "1") (pinfunction "1_1") (pintype "passive"))
      (node (ref "J4") (pin "2") (pinfunction "I/O_2") (pintype "passive"))
      (node (ref "R54") (pin "2") (pinfunction "2_2") (pintype "passive"))
    )
    (net (code "10") (name "/NB_POWER") (class "Default")
      (node (ref "R88") (pin "2") (pinfunction "2_2") (pintype "passive"))
    )
    (net (code "11") (name "/PWR_CTL") (class "Default")
      (node (ref "U6") (pin "6") (pinfunction "PWR_CTL_6") (pintype "passive"))
    )
    (net (code "12") (name "/SLE_BUSY") (class "Default")
      (node (ref "U6") (pin "23") (pinfunction "BUSY_IND_23") (pintype "passive"))
    )
    (net (code "13") (name "/SLE_DOUT") (class "Default")
      (node (ref "U6") (pin "22") (pinfunction "DOUT_IND_22") (pintype "passive"))
    )
    (net (code "14") (name "/SLE_PWR") (class "Default")
      (node (ref "U6") (pin "21") (pinfunction "PWR_IND_21") (pintype "passive"))
    )
    (net (code "15") (name "/SLE_RST") (class "Default")
      (node (ref "R93") (pin "1") (pinfunction "1_1") (pintype "passive"))
    )
    (net (code "16") (name "/STATE_BLE") (class "Default")
      (node (ref "U13") (pin "10") (pinfunction "P0.05/AIN3_10") (pintype "passive"))
    )
    (net (code "17") (name "/S_R") (class "Default")
      (node (ref "J5") (pin "2") (pinfunction "2_2") (pintype "passive"))
      (node (ref "U6") (pin "25") (pinfunction "UART_L0_RXD_25") (pintype "passive"))
    )
    (net (code "18") (name "/S_T") (class "Default")
      (node (ref "J5") (pin "3") (pinfunction "3_3") (pintype "passive"))
      (node (ref "U6") (pin "24") (pinfunction "UART_L0_TXD_24") (pintype "passive"))
    )
    (net (code "19") (name "/VDD_BLE_CTL") (class "Default")
      (node (ref "R31") (pin "1") (pinfunction "1_1") (pintype "passive"))
    )
    (net (code "20") (name "/VDD_SLE") (class "Default")
      (node (ref "C81") (pin "1") (pinfunction "1_1") (pintype "passive"))
      (node (ref "C82") (pin "1") (pinfunction "1_1") (pintype "passive"))
      (node (ref "C83") (pin "1") (pinfunction "1_1") (pintype "passive"))
      (node (ref "Q30") (pin "3") (pinfunction "D_3") (pintype "passive"))
      (node (ref "R95") (pin "1") (pinfunction "1_1") (pintype "passive"))
      (node (ref "R96") (pin "1") (pinfunction "1_1") (pintype "passive"))
      (node (ref "U6") (pin "10") (pinfunction "VBAT_10") (pintype "passive"))
    )
    (net (code "21") (name "/VDD_SLE_CTL") (class "Default")
      (node (ref "R92") (pin "1") (pinfunction "1_1") (pintype "passive"))
    )
    (net (code "22") (name "/VIN_ADC") (class "Default")
      (node (ref "C36") (pin "2") (pinfunction "2_2") (pintype "passive"))
      (node (ref "R67") (pin "2") (pinfunction "2_2") (pintype "passive"))
      (node (ref "R73") (pin "1") (pinfunction "1_1") (pintype "passive"))
    )
    (net (code "23") (name "/VIN_CHECK_EN") (class "Default")
      (node (ref "R74") (pin "1") (pinfunction "1_1") (pintype "passive"))
    )
    (net (code "24") (name "5V") (class "Default")
      (node (ref "5V") (pin "1") (pinfunction "1_1") (pintype "passive"))
      (node (ref "D11") (pin "1") (pinfunction "1_1") (pintype "passive"))
      (node (ref "D15") (pin "1") (pinfunction "1_1") (pintype "passive"))
      (node (ref "R106") (pin "2") (pinfunction "2_2") (pintype "passive"))
      (node (ref "R42") (pin "2") (pinfunction "2_2") (pintype "passive"))
      (node (ref "U4") (pin "3") (pinfunction "Vout_3") (pintype "passive"))
    )
    (net (code "25") (name "GND") (class "Default")
      (node (ref "C100") (pin "2") (pinfunction "2_2") (pintype "passive"))
      (node (ref "C102") (pin "2") (pinfunction "2_2") (pintype "passive"))
      (node (ref "C23") (pin "2") (pinfunction "2_2") (pintype "passive"))
      (node (ref "C29") (pin "1") (pinfunction "1_1") (pintype "passive"))
      (node (ref "C36") (pin "1") (pinfunction "1_1") (pintype "passive"))
      (node (ref "C41") (pin "2") (pinfunction "2_2") (pintype "passive"))
      (node (ref "C49") (pin "1") (pinfunction "1_1") (pintype "passive"))
      (node (ref "C50") (pin "2") (pinfunction "2_2") (pintype "passive"))
      (node (ref "C52") (pin "2") (pinfunction "2_2") (pintype "passive"))
      (node (ref "C55") (pin "1") (pinfunction "1_1") (pintype "passive"))
      (node (ref "C63") (pin "2") (pinfunction "2_2") (pintype "passive"))
      (node (ref "C65") (pin "2") (pinfunction "2_2") (pintype "passive"))
      (node (ref "C71") (pin "1") (pinfunction "1_1") (pintype "passive"))
      (node (ref "C75") (pin "2") (pinfunction "2_2") (pintype "passive"))
      (node (ref "C77") (pin "2") (pinfunction "2_2") (pintype "passive"))
      (node (ref "C78") (pin "2") (pinfunction "2_2") (pintype "passive"))
      (node (ref "C81") (pin "2") (pinfunction "2_2") (pintype "passive"))
      (node (ref "C82") (pin "2") (pinfunction "2_2") (pintype "passive"))
      (node (ref "C83") (pin "2") (pinfunction "2_2") (pintype "passive"))
      (node (ref "C91") (pin "2") (pinfunction "2_2") (pintype "passive"))
      (node (ref "C95") (pin "2") (pinfunction "2_2") (pintype "passive"))
      (node (ref "C96") (pin "1") (pinfunction "1_1") (pintype "passive"))
      (node (ref "C98") (pin "2") (pinfunction "2_2") (pintype "passive"))
      (node (ref "C99") (pin "2") (pinfunction "2_2") (pintype "passive"))
      (node (ref "GND") (pin "1") (pinfunction "1_1") (pintype "passive"))
      (node (ref "J4") (pin "5") (pinfunction "GND_5") (pintype "passive"))
      (node (ref "J5") (pin "1") (pinfunction "1_1") (pintype "passive"))
      (node (ref "J6") (pin "2") (pinfunction "2_2") (pintype "passive"))
      (node (ref "P2") (pin "2") (pinfunction "2_2") (pintype "passive"))
      (node (ref "Q13") (pin "2") (pinfunction "E_2") (pintype "passive"))
      (node (ref "Q16") (pin "2") (pinfunction "E_2") (pintype "passive"))
      (node (ref "Q27") (pin "2") (pinfunction "S_2") (pintype "passive"))
      (node (ref "Q29") (pin "2") (pinfunction "S_2") (pintype "passive"))
      (node (ref "Q31") (pin "2") (pinfunction "E_2") (pintype "passive"))
      (node (ref "R116") (pin "2") (pinfunction "2_2") (pintype "passive"))
      (node (ref "R73") (pin "2") (pinfunction "2_2") (pintype "passive"))
      (node (ref "R78") (pin "2") (pinfunction "2_2") (pintype "passive"))
      (node (ref "R94") (pin "2") (pinfunction "2_2") (pintype "passive"))
      (node (ref "R99") (pin "1") (pinfunction "1_1") (pintype "passive"))
      (node (ref "TVS1") (pin "1") (pinfunction "1_1") (pintype "passive"))
      (node (ref "U13") (pin "1") (pinfunction "GND_1") (pintype "passive"))
      (node (ref "U13") (pin "15") (pinfunction "GND_15") (pintype "passive"))
      (node (ref "U4") (pin "1") (pinfunction "GND_1") (pintype "passive"))
      (node (ref "U6") (pin "11") (pinfunction "GND_11") (pintype "passive"))
      (node (ref "U6") (pin "2") (pinfunction "GND_2") (pintype "passive"))
      (node (ref "U6") (pin "26") (pinfunction "GND_26") (pintype "passive"))
      (node (ref "U6") (pin "29") (pinfunction "GND_29") (pintype "passive"))
      (node (ref "U6") (pin "30") (pinfunction "GND_30") (pintype "passive"))
      (node (ref "U6") (pin "31") (pinfunction "GND_31") (pintype "passive"))
      (node (ref "U6") (pin "33") (pinfunction "GND_TP_33") (pintype "passive"))
      (node (ref "U6") (pin "38") (pinfunction "GND_38") (pintype "passive"))
      (node (ref "U9") (pin "1") (pinfunction "GND_1") (pintype "passive"))
    )
    (net (code "26") (name "NB_VIN1") (class "Default")
      (node (ref "Q23") (pin "3") (pinfunction "D_3") (pintype "passive"))
    )
    (net (code "27") (name "Net-(C90-Pad1)") (class "Default")
      (node (ref "C90") (pin "1") (pinfunction "1_1") (pintype "passive"))
      (node (ref "R106") (pin "1") (pinfunction "1_1") (pintype "passive"))
    )
    (net (code "28") (name "Net-(C90-Pad2)") (class "Default")
      (node (ref "C90") (pin "2") (pinfunction "2_2") (pintype "passive"))
      (node (ref "C91") (pin "1") (pinfunction "1_1") (pintype "passive"))
    )
    (net (code "29") (name "Net-(D18-Pad1)") (class "Default")
      (node (ref "D18") (pin "1") (pinfunction "1_1") (pintype "passive"))
      (node (ref "R44") (pin "1") (pinfunction "1_1") (pintype "passive"))
    )
    (net (code "30") (name "Net-(D41-Pad1)") (class "Default")
      (node (ref "D41") (pin "1") (pinfunction "1_1") (pintype "passive"))
      (node (ref "P10") (pin "2") (pinfunction "2_2") (pintype "passive"))
      (node (ref "R105") (pin "2") (pinfunction "2_2") (pintype "passive"))
    )
    (net (code "31") (name "Net-(P5-Pad2)") (class "Default")
      (node (ref "P5") (pin "2") (pinfunction "2_2") (pintype "passive"))
      (node (ref "P5") (pin "3") (pinfunction "3_3") (pintype "passive"))
      (node (ref "P6") (pin "1") (pinfunction "1_1") (pintype "passive"))
      (node (ref "R118") (pin "1") (pinfunction "1_1") (pintype "passive"))
      (node (ref "R122") (pin "2") (pinfunction "2_2") (pintype "passive"))
    )
    (net (code "32") (name "Net-(Q8-G)") (class "Default")
      (node (ref "Q8") (pin "1") (pinfunction "G_1") (pintype "passive"))
      (node (ref "R31") (pin "2") (pinfunction "2_2") (pintype "passive"))
      (node (ref "R35") (pin "2") (pinfunction "2_2") (pintype "passive"))
    )
    (net (code "33") (name "Net-(Q11-B)") (class "Default")
      (node (ref "Q11") (pin "1") (pinfunction "B_1") (pintype "passive"))
      (node (ref "R70") (pin "2") (pinfunction "2_2") (pintype "passive"))
    )
    (net (code "34") (name "Net-(Q11-C)") (class "Default")
      (node (ref "Q11") (pin "3") (pinfunction "C_3") (pintype "passive"))
      (node (ref "R67") (pin "1") (pinfunction "1_1") (pintype "passive"))
    )
    (net (code "35") (name "Net-(Q13-B)") (class "Default")
      (node (ref "Q13") (pin "1") (pinfunction "B_1") (pintype "passive"))
      (node (ref "R74") (pin "2") (pinfunction "2_2") (pintype "passive"))
      (node (ref "R78") (pin "1") (pinfunction "1_1") (pintype "passive"))
    )
    (net (code "36") (name "Net-(Q13-C)") (class "Default")
      (node (ref "D10") (pin "1") (pinfunction "1_1") (pintype "passive"))
      (node (ref "Q13") (pin "3") (pinfunction "C_3") (pintype "passive"))
      (node (ref "R70") (pin "1") (pinfunction "1_1") (pintype "passive"))
    )
    (net (code "37") (name "Net-(Q16-B)") (class "Default")
      (node (ref "Q16") (pin "1") (pinfunction "B_1") (pintype "passive"))
      (node (ref "R88") (pin "1") (pinfunction "1_1") (pintype "passive"))
    )
    (net (code "38") (name "Net-(Q16-C)") (class "Default")
      (node (ref "Q16") (pin "3") (pinfunction "C_3") (pintype "passive"))
      (node (ref "R86") (pin "1") (pinfunction "1_1") (pintype "passive"))
    )
    (net (code "39") (name "Net-(Q17-B)") (class "Default")
      (node (ref "Q17") (pin "1") (pinfunction "B_1") (pintype "passive"))
      (node (ref "R108") (pin "1") (pinfunction "1_1") (pintype "passive"))
      (node (ref "R44") (pin "2") (pinfunction "2_2") (pintype "passive"))
    )
    (net (code "40") (name "Net-(Q17-C)") (class "Default")
      (node (ref "Q17") (pin "3") (pinfunction "C_3") (pintype "passive"))
      (node (ref "R51") (pin "2") (pinfunction "2_2") (pintype "passive"))
      (node (ref "R53") (pin "1") (pinfunction "1_1") (pintype "passive"))
      (node (ref "R54") (pin "1") (pinfunction "1_1") (pintype "passive"))
      (node (ref "R75") (pin "1") (pinfunction "1_1") (pintype "passive"))
    )
    (net (code "41") (name "Net-(Q23-G)") (class "Default")
      (node (ref "Q23") (pin "1") (pinfunction "G_1") (pintype "passive"))
      (node (ref "R85") (pin "2") (pinfunction "2_2") (pintype "passive"))
      (node (ref "R86") (pin "2") (pinfunction "2_2") (pintype "passive"))
    )
    (net (code "42") (name "Net-(Q26-D)") (class "Default")
      (node (ref "Q26") (pin "3") (pinfunction "D_3") (pintype "passive"))
      (node (ref "Q27") (pin "3") (pinfunction "D_3") (pintype "passive"))
      (node (ref "R120") (pin "2") (pinfunction "2_2") (pintype "passive"))
    )
    (net (code "43") (name "Net-(Q26-G)") (class "Default")
      (node (ref "Q26") (pin "1") (pinfunction "G_1") (pintype "passive"))
      (node (ref "TP5") (pin "1") (pinfunction "1_1") (pintype "passive"))
      (node (ref "U7") (pin "1") (pinfunction "DOUT_1") (pintype "passive"))
    )
    (net (code "44") (name "Net-(Q27-G)") (class "Default")
      (node (ref "Q27") (pin "1") (pinfunction "G_1") (pintype "passive"))
      (node (ref "TP4") (pin "1") (pinfunction "1_1") (pintype "passive"))
      (node (ref "U7") (pin "2") (pinfunction "COUT_2") (pintype "passive"))
    )
    (net (code "45") (name "Net-(Q28-D)") (class "Default")
      (node (ref "Q28") (pin "3") (pinfunction "D_3") (pintype "passive"))
      (node (ref "Q29") (pin "3") (pinfunction "D_3") (pintype "passive"))
      (node (ref "R121") (pin "2") (pinfunction "2_2") (pintype "passive"))
    )
    (net (code "46") (name "Net-(Q28-G)") (class "Default")
      (node (ref "Q28") (pin "1") (pinfunction "G_1") (pintype "passive"))
      (node (ref "U19") (pin "1") (pinfunction "DOUT_1") (pintype "passive"))
    )
    (net (code "47") (name "Net-(Q29-G)") (class "Default")
      (node (ref "Q29") (pin "1") (pinfunction "G_1") (pintype "passive"))
      (node (ref "U19") (pin "3") (pinfunction "COUT_3") (pintype "passive"))
    )
    (net (code "48") (name "Net-(Q30-G)") (class "Default")
      (node (ref "Q30") (pin "1") (pinfunction "G_1") (pintype "passive"))
      (node (ref "R91") (pin "1") (pinfunction "1_1") (pintype "passive"))
      (node (ref "R92") (pin "2") (pinfunction "2_2") (pintype "passive"))
    )
    (net (code "49") (name "Net-(Q31-B)") (class "Default")
      (node (ref "Q31") (pin "1") (pinfunction "B_1") (pintype "passive"))
      (node (ref "R93") (pin "2") (pinfunction "2_2") (pintype "passive"))
      (node (ref "R94") (pin "1") (pinfunction "1_1") (pintype "passive"))
    )
    (net (code "50") (name "Net-(Q31-C)") (class "Default")
      (node (ref "Q31") (pin "3") (pinfunction "C_3") (pintype "passive"))
      (node (ref "U6") (pin "12") (pinfunction "nRESET_12") (pintype "passive"))
    )
    (net (code "51") (name "Net-(U7-V-)") (class "Default")
      (node (ref "C69") (pin "1") (pinfunction "1_1") (pintype "passive"))
      (node (ref "R116") (pin "1") (pinfunction "1_1") (pintype "passive"))
      (node (ref "U7") (pin "3") (pinfunction "V-_3") (pintype "passive"))
    )
    (net (code "52") (name "Net-(U7-VBL)") (class "Default")
      (node (ref "C67") (pin "2") (pinfunction "2_2") (pintype "passive"))
      (node (ref "R118") (pin "2") (pinfunction "2_2") (pintype "passive"))
      (node (ref "U7") (pin "4") (pinfunction "VBL_4") (pintype "passive"))
    )
    (net (code "53") (name "Net-(U7-VDD)") (class "Default")
      (node (ref "C68") (pin "2") (pinfunction "2_2") (pintype "passive"))
      (node (ref "R117") (pin "2") (pinfunction "2_2") (pintype "passive"))
      (node (ref "U7") (pin "5") (pinfunction "VDD_5") (pintype "passive"))
    )
    (net (code "54") (name "Net-(U9-Vin)") (class "Default")
      (node (ref "C41") (pin "1") (pinfunction "1_1") (pintype "passive"))
      (node (ref "D11") (pin "2") (pinfunction "2_2") (pintype "passive"))
      (node (ref "TP1") (pin "1") (pinfunction "1_1") (pintype "passive"))
      (node (ref "U9") (pin "2") (pinfunction "Vin_2") (pintype "passive"))
    )
    (net (code "55") (name "Net-(U19-V-)") (class "Default")
      (node (ref "R99") (pin "2") (pinfunction "2_2") (pintype "passive"))
      (node (ref "U19") (pin "2") (pinfunction "V-_2") (pintype "passive"))
    )
    (net (code "56") (name "Net-(U19-VDD)") (class "Default")
      (node (ref "C72") (pin "2") (pinfunction "2_2") (pintype "passive"))
      (node (ref "R119") (pin "2") (pinfunction "2_2") (pintype "passive"))
      (node (ref "U19") (pin "5") (pinfunction "VDD_5") (pintype "passive"))
    )
    (net (code "57") (name "PGND") (class "Default")
      (node (ref "C67") (pin "1") (pinfunction "1_1") (pintype "passive"))
      (node (ref "C68") (pin "1") (pinfunction "1_1") (pintype "passive"))
      (node (ref "C69") (pin "2") (pinfunction "2_2") (pintype "passive"))
      (node (ref "C72") (pin "1") (pinfunction "1_1") (pintype "passive"))
      (node (ref "P6") (pin "2") (pinfunction "2_2") (pintype "passive"))
      (node (ref "P6") (pin "3") (pinfunction "3_3") (pintype "passive"))
      (node (ref "PGND") (pin "1") (pinfunction "1_1") (pintype "passive"))
      (node (ref "Q26") (pin "2") (pinfunction "S_2") (pintype "passive"))
      (node (ref "Q28") (pin "2") (pinfunction "S_2") (pintype "passive"))
      (node (ref "R120") (pin "1") (pinfunction "1_1") (pintype "passive"))
      (node (ref "R121") (pin "1") (pinfunction "1_1") (pintype "passive"))
      (node (ref "R122") (pin "1") (pinfunction "1_1") (pintype "passive"))
      (node (ref "U19") (pin "6") (pinfunction "VSS_6") (pintype "passive"))
      (node (ref "U7") (pin "6") (pinfunction "VSS_6") (pintype "passive"))
    )
    (net (code "58") (name "S+") (class "Default")
      (node (ref "C71") (pin "2") (pinfunction "2_2") (pintype "passive"))
      (node (ref "P10") (pin "1") (pinfunction "1_1") (pintype "passive"))
      (node (ref "P5") (pin "1") (pinfunction "1_1") (pintype "passive"))
      (node (ref "R117") (pin "1") (pinfunction "1_1") (pintype "passive"))
      (node (ref "R119") (pin "1") (pinfunction "1_1") (pintype "passive"))
      (node (ref "S+") (pin "1") (pinfunction "1_1") (pintype "passive"))
    )
    (net (code "59") (name "VCC") (class "Default")
      (node (ref "C49") (pin "2") (pinfunction "2_2") (pintype "passive"))
      (node (ref "C50") (pin "1") (pinfunction "1_1") (pintype "passive"))
      (node (ref "C52") (pin "1") (pinfunction "1_1") (pintype "passive"))
      (node (ref "C55") (pin "2") (pinfunction "2_2") (pintype "passive"))
      (node (ref "Q17") (pin "2") (pinfunction "E_2") (pintype "passive"))
      (node (ref "Q30") (pin "2") (pinfunction "S_2") (pintype "passive"))
      (node (ref "Q8") (pin "2") (pinfunction "S_2") (pintype "passive"))
      (node (ref "R108") (pin "2") (pinfunction "2_2") (pintype "passive"))
      (node (ref "R35") (pin "1") (pinfunction "1_1") (pintype "passive"))
      (node (ref "R55") (pin "2") (pinfunction "2_2") (pintype "passive"))
      (node (ref "R91") (pin "2") (pinfunction "2_2") (pintype "passive"))
      (node (ref "U9") (pin "3") (pinfunction "Vout_3") (pintype "passive"))
      (node (ref "VCC") (pin "1") (pinfunction "1_1") (pintype "passive"))
    )
    (net (code "60") (name "VDD_BLE") (class "Default")
      (node (ref "C63") (pin "1") (pinfunction "1_1") (pintype "passive"))
      (node (ref "C65") (pin "1") (pinfunction "1_1") (pintype "passive"))
      (node (ref "Q8") (pin "3") (pinfunction "D_3") (pintype "passive"))
      (node (ref "U13") (pin "14") (pinfunction "VDD_14") (pintype "passive"))
    )
    (net (code "61") (name "VIN") (class "Default")
      (node (ref "D10") (pin "2") (pinfunction "2_2") (pintype "passive"))
      (node (ref "D14") (pin "1") (pinfunction "1_1") (pintype "passive"))
      (node (ref "P2") (pin "1") (pinfunction "1_1") (pintype "passive"))
      (node (ref "Q11") (pin "2") (pinfunction "E_2") (pintype "passive"))
      (node (ref "TVS1") (pin "2") (pinfunction "2_2") (pintype "passive"))
      (node (ref "VIN") (pin "1") (pinfunction "1_1") (pintype "passive"))
    )
    (net (code "62") (name "VIN_NB") (class "Default")
      (node (ref "C102") (pin "1") (pinfunction "1_1") (pintype "passive"))
      (node (ref "C23") (pin "1") (pinfunction "1_1") (pintype "passive"))
      (node (ref "C75") (pin "1") (pinfunction "1_1") (pintype "passive"))
      (node (ref "C77") (pin "1") (pinfunction "1_1") (pintype "passive"))
      (node (ref "D14") (pin "2") (pinfunction "2_2") (pintype "passive"))
      (node (ref "D15") (pin "2") (pinfunction "2_2") (pintype "passive"))
      (node (ref "D41") (pin "2") (pinfunction "2_2") (pintype "passive"))
      (node (ref "Q23") (pin "2") (pinfunction "S_2") (pintype "passive"))
      (node (ref "R105") (pin "1") (pinfunction "1_1") (pintype "passive"))
      (node (ref "R42") (pin "1") (pinfunction "1_1") (pintype "passive"))
      (node (ref "R85") (pin "1") (pinfunction "1_1") (pintype "passive"))
      (node (ref "U4") (pin "2") (pinfunction "Vin_2") (pintype "passive"))
    )
    (net (code "63") (name "VRTC") (class "Default")
      (node (ref "C78") (pin "1") (pinfunction "1_1") (pintype "passive"))
      (node (ref "J6") (pin "1") (pinfunction "1_1") (pintype "passive"))
      (node (ref "VRTC") (pin "1") (pinfunction "1_1") (pintype "passive"))
    )
    (net (code "64") (name "unconnected-(U6A-ANT-Pad27)") (class "Default")
      (node (ref "U6") (pin "27") (pinfunction "ANT_27") (pintype "passive"))
    )
    (net (code "65") (name "unconnected-(U6A-MIC_LDO-Pad1)") (class "Default")
      (node (ref "U6") (pin "1") (pinfunction "MIC_LDO_1") (pintype "passive"))
    )
    (net (code "66") (name "unconnected-(U6A-REV-Pad3)") (class "Default")
      (node (ref "U6") (pin "3") (pinfunction "REV_3") (pintype "passive"))
    )
    (net (code "67") (name "unconnected-(U6A-REV-Pad4)") (class "Default")
      (node (ref "U6") (pin "4") (pinfunction "REV_4") (pintype "passive"))
    )
    (net (code "68") (name "unconnected-(U6A-REV-Pad5)") (class "Default")
      (node (ref "U6") (pin "5") (pinfunction "REV_5") (pintype "passive"))
    )
    (net (code "69") (name "unconnected-(U6A-REV-Pad19)") (class "Default")
      (node (ref "U6") (pin "19") (pinfunction "REV_19") (pintype "passive"))
    )
    (net (code "70") (name "unconnected-(U6A-REV-Pad20)") (class "Default")
      (node (ref "U6") (pin "20") (pinfunction "REV_20") (pintype "passive"))
    )
    (net (code "71") (name "unconnected-(U6A-SWCLK-Pad13)") (class "Default")
      (node (ref "U6") (pin "13") (pinfunction "SWCLK_13") (pintype "passive"))
    )
    (net (code "72") (name "unconnected-(U6A-SWDIO-Pad14)") (class "Default")
      (node (ref "U6") (pin "14") (pinfunction "SWDIO_14") (pintype "passive"))
    )
    (net (code "73") (name "unconnected-(U6A-TEST_IO-Pad9)") (class "Default")
      (node (ref "U6") (pin "9") (pinfunction "TEST_IO_9") (pintype "passive"))
    )
    (net (code "74") (name "unconnected-(U6A-UART_L1_RXD-Pad8)") (class "Default")
      (node (ref "U6") (pin "8") (pinfunction "UART_L1_RXD_8") (pintype "passive"))
    )
    (net (code "75") (name "unconnected-(U6A-UART_L1_TXD-Pad7)") (class "Default")
      (node (ref "U6") (pin "7") (pinfunction "UART_L1_TXD_7") (pintype "passive"))
    )
    (net (code "76") (name "unconnected-(U6A-USB_DN-Pad16)") (class "Default")
      (node (ref "U6") (pin "16") (pinfunction "USB_DN_16") (pintype "passive"))
    )
    (net (code "77") (name "unconnected-(U6A-USB_DP-Pad15)") (class "Default")
      (node (ref "U6") (pin "15") (pinfunction "USB_DP_15") (pintype "passive"))
    )
    (net (code "78") (name "unconnected-(U6B-ANT_TP-Pad32)") (class "Default")
      (node (ref "U6") (pin "32") (pinfunction "ANT_TP_32") (pintype "passive"))
    )
    (net (code "79") (name "unconnected-(U6B-NC-Pad28)") (class "Default")
      (node (ref "U6") (pin "28") (pinfunction "NC_28") (pintype "passive"))
    )
    (net (code "80") (name "unconnected-(U6B-NC-Pad44)") (class "Default")
      (node (ref "U6") (pin "44") (pinfunction "NC_44") (pintype "passive"))
    )
    (net (code "81") (name "unconnected-(U6B-NC-Pad45)") (class "Default")
      (node (ref "U6") (pin "45") (pinfunction "NC_45") (pintype "passive"))
    )
    (net (code "82") (name "unconnected-(U6B-REV-Pad34)") (class "Default")
      (node (ref "U6") (pin "34") (pinfunction "REV_34") (pintype "passive"))
    )
    (net (code "83") (name "unconnected-(U6B-REV-Pad35)") (class "Default")
      (node (ref "U6") (pin "35") (pinfunction "REV_35") (pintype "passive"))
    )
    (net (code "84") (name "unconnected-(U6B-REV-Pad36)") (class "Default")
      (node (ref "U6") (pin "36") (pinfunction "REV_36") (pintype "passive"))
    )
    (net (code "85") (name "unconnected-(U6B-REV-Pad37)") (class "Default")
      (node (ref "U6") (pin "37") (pinfunction "REV_37") (pintype "passive"))
    )
    (net (code "86") (name "unconnected-(U6B-REV-Pad39)") (class "Default")
      (node (ref "U6") (pin "39") (pinfunction "REV_39") (pintype "passive"))
    )
    (net (code "87") (name "unconnected-(U6B-REV-Pad40)") (class "Default")
      (node (ref "U6") (pin "40") (pinfunction "REV_40") (pintype "passive"))
    )
    (net (code "88") (name "unconnected-(U6B-REV-Pad41)") (class "Default")
      (node (ref "U6") (pin "41") (pinfunction "REV_41") (pintype "passive"))
    )
    (net (code "89") (name "unconnected-(U6B-REV-Pad43)") (class "Default")
      (node (ref "U6") (pin "43") (pinfunction "REV_43") (pintype "passive"))
    )
    (net (code "90") (name "unconnected-(U6B-REV-Pad46)") (class "Default")
      (node (ref "U6") (pin "46") (pinfunction "REV_46") (pintype "passive"))
    )
    (net (code "91") (name "unconnected-(U6B-REV-Pad47)") (class "Default")
      (node (ref "U6") (pin "47") (pinfunction "REV_47") (pintype "passive"))
    )
    (net (code "92") (name "unconnected-(U6B-TEST_IO-Pad42)") (class "Default")
      (node (ref "U6") (pin "42") (pinfunction "TEST_IO_42") (pintype "passive"))
    )
    (net (code "93") (name "unconnected-(U13-P0.00{slash}XL1-Pad13)") (class "Default")
      (node (ref "U13") (pin "13") (pinfunction "P0.00/XL1_13") (pintype "passive"))
    )
    (net (code "94") (name "unconnected-(U13-P0.01{slash}XL2-Pad12)") (class "Default")
      (node (ref "U13") (pin "12") (pinfunction "P0.01/XL2_12") (pintype "passive"))
    )
    (net (code "95") (name "unconnected-(U13-P0.16-Pad7)") (class "Default")
      (node (ref "U13") (pin "7") (pinfunction "P0.16_7") (pintype "passive"))
    )
    (net (code "96") (name "unconnected-(U13-P0.18-Pad6)") (class "Default")
      (node (ref "U13") (pin "6") (pinfunction "P0.18_6") (pintype "passive"))
    )
    (net (code "97") (name "unconnected-(U13-P0.20-Pad5)") (class "Default")
      (node (ref "U13") (pin "5") (pinfunction "P0.20_5") (pintype "passive"))
    )
    (net (code "98") (name "unconnected-(U13-SWCLK-Pad3)") (class "Default")
      (node (ref "U13") (pin "3") (pinfunction "SWCLK_3") (pintype "passive"))
    )
    (net (code "99") (name "unconnected-(U13-SWDIO-Pad2)") (class "Default")
      (node (ref "U13") (pin "2") (pinfunction "SWDIO_2") (pintype "passive"))
    )
    (net (code "100") (name "unconnected-(U13-nRESET-Pad4)") (class "Default")
      (node (ref "U13") (pin "4") (pinfunction "nRESET_4") (pintype "passive"))
    )
    (net (code "101") (name "unconnected-(U19-NC-Pad4)") (class "Default")
      (node (ref "U19") (pin "4") (pinfunction "NC_4") (pintype "passive+no_connect"))
    )
  )
)
